# clock_board.net
KiCad netlist of a schematic drawn in EAGLE
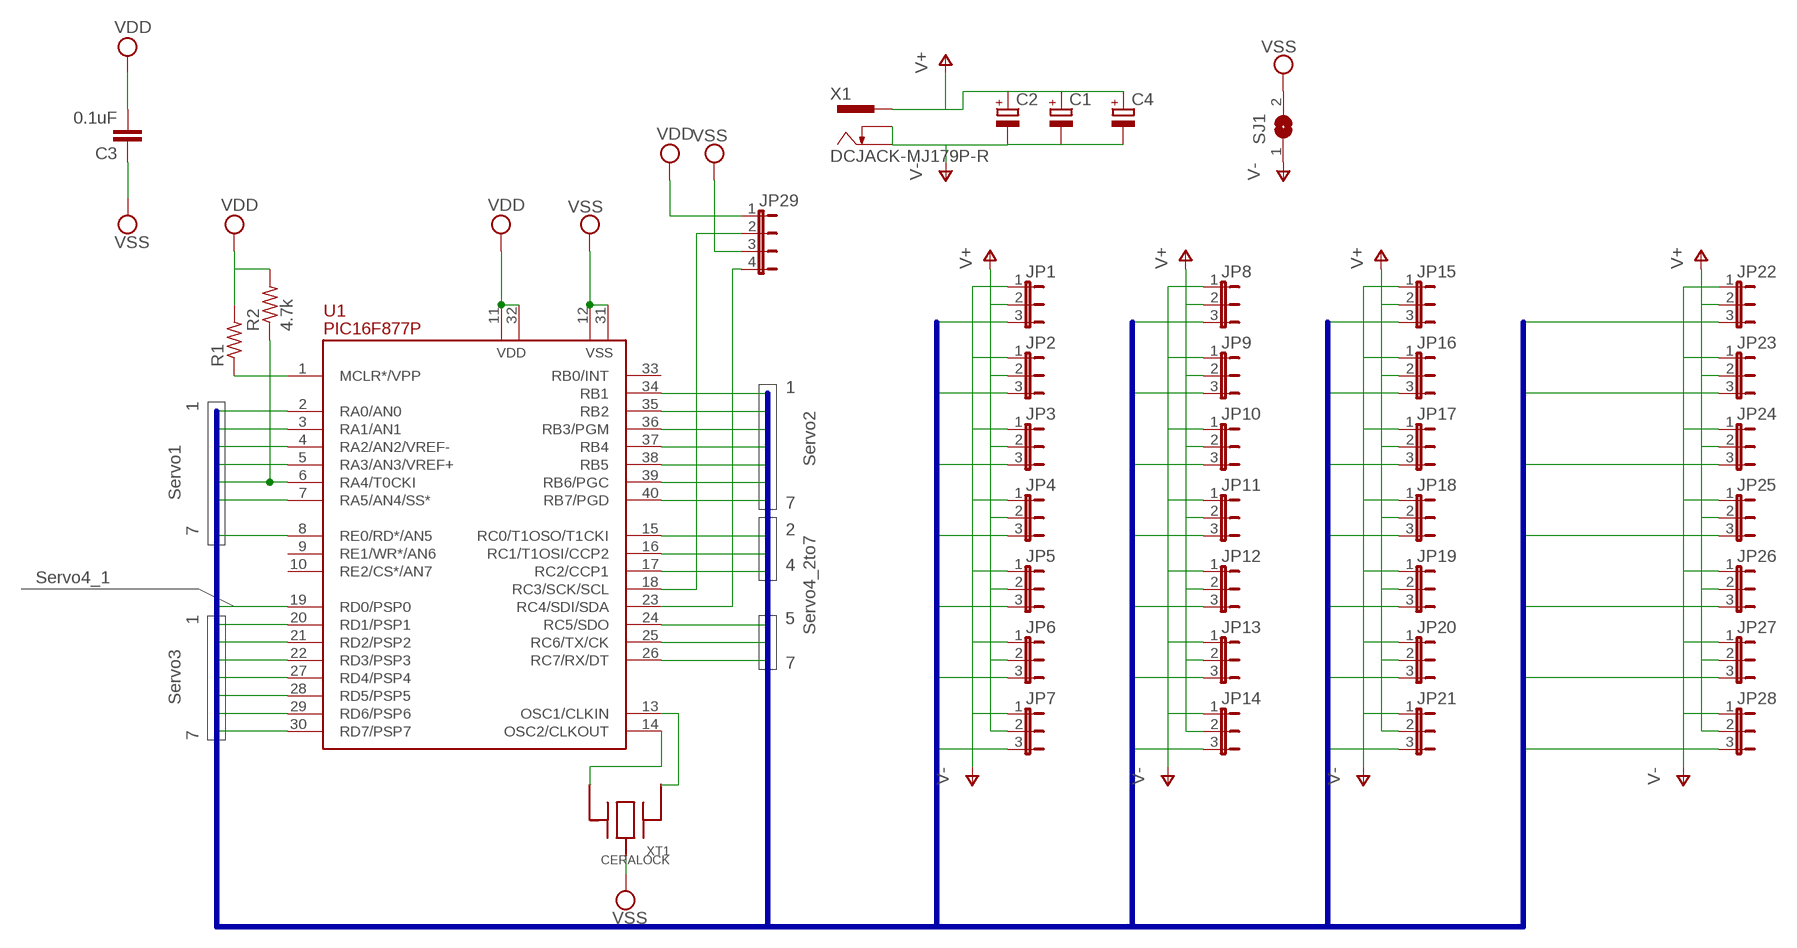
[diagram p0: schematic, sheet 1]

(export (version "E")
  (design (tool "Eeschema 10.0.6"))
  (components
    (comp (ref "C1")
      (value "CPOL-EUE2.5-5")
      (footprint "eagle-import:E2,5-5")
      (libsource (lib "eagle-import") (part "CPOL-EUE2.5-5"))
    )
    (comp (ref "C2")
      (value "CPOL-EUE2.5-5")
      (footprint "eagle-import:E2,5-5")
      (libsource (lib "eagle-import") (part "CPOL-EUE2.5-5"))
    )
    (comp (ref "C3")
      (value "0.1uF")
      (footprint "eagle-import:C025-024X044")
      (libsource (lib "eagle-import") (part "C-EU025-024X044"))
    )
    (comp (ref "C4")
      (value "CPOL-EUE2.5-5")
      (footprint "eagle-import:E2,5-5")
      (libsource (lib "eagle-import") (part "CPOL-EUE2.5-5"))
    )
    (comp (ref "JP1")
      (value "JP2E")
      (footprint "eagle-import:JP2")
      (libsource (lib "eagle-import") (part "JP2E"))
    )
    (comp (ref "JP2")
      (value "JP2E")
      (footprint "eagle-import:JP2")
      (libsource (lib "eagle-import") (part "JP2E"))
    )
    (comp (ref "JP3")
      (value "JP2E")
      (footprint "eagle-import:JP2")
      (libsource (lib "eagle-import") (part "JP2E"))
    )
    (comp (ref "JP4")
      (value "JP2E")
      (footprint "eagle-import:JP2")
      (libsource (lib "eagle-import") (part "JP2E"))
    )
    (comp (ref "JP5")
      (value "JP2E")
      (footprint "eagle-import:JP2")
      (libsource (lib "eagle-import") (part "JP2E"))
    )
    (comp (ref "JP6")
      (value "JP2E")
      (footprint "eagle-import:JP2")
      (libsource (lib "eagle-import") (part "JP2E"))
    )
    (comp (ref "JP7")
      (value "JP2E")
      (footprint "eagle-import:JP2")
      (libsource (lib "eagle-import") (part "JP2E"))
    )
    (comp (ref "JP8")
      (value "JP2E")
      (footprint "eagle-import:JP2")
      (libsource (lib "eagle-import") (part "JP2E"))
    )
    (comp (ref "JP9")
      (value "JP2E")
      (footprint "eagle-import:JP2")
      (libsource (lib "eagle-import") (part "JP2E"))
    )
    (comp (ref "JP10")
      (value "JP2E")
      (footprint "eagle-import:JP2")
      (libsource (lib "eagle-import") (part "JP2E"))
    )
    (comp (ref "JP11")
      (value "JP2E")
      (footprint "eagle-import:JP2")
      (libsource (lib "eagle-import") (part "JP2E"))
    )
    (comp (ref "JP12")
      (value "JP2E")
      (footprint "eagle-import:JP2")
      (libsource (lib "eagle-import") (part "JP2E"))
    )
    (comp (ref "JP13")
      (value "JP2E")
      (footprint "eagle-import:JP2")
      (libsource (lib "eagle-import") (part "JP2E"))
    )
    (comp (ref "JP14")
      (value "JP2E")
      (footprint "eagle-import:JP2")
      (libsource (lib "eagle-import") (part "JP2E"))
    )
    (comp (ref "JP15")
      (value "JP2E")
      (footprint "eagle-import:JP2")
      (libsource (lib "eagle-import") (part "JP2E"))
    )
    (comp (ref "JP16")
      (value "JP2E")
      (footprint "eagle-import:JP2")
      (libsource (lib "eagle-import") (part "JP2E"))
    )
    (comp (ref "JP17")
      (value "JP2E")
      (footprint "eagle-import:JP2")
      (libsource (lib "eagle-import") (part "JP2E"))
    )
    (comp (ref "JP18")
      (value "JP2E")
      (footprint "eagle-import:JP2")
      (libsource (lib "eagle-import") (part "JP2E"))
    )
    (comp (ref "JP19")
      (value "JP2E")
      (footprint "eagle-import:JP2")
      (libsource (lib "eagle-import") (part "JP2E"))
    )
    (comp (ref "JP20")
      (value "JP2E")
      (footprint "eagle-import:JP2")
      (libsource (lib "eagle-import") (part "JP2E"))
    )
    (comp (ref "JP21")
      (value "JP2E")
      (footprint "eagle-import:JP2")
      (libsource (lib "eagle-import") (part "JP2E"))
    )
    (comp (ref "JP22")
      (value "JP2E")
      (footprint "eagle-import:JP2")
      (libsource (lib "eagle-import") (part "JP2E"))
    )
    (comp (ref "JP23")
      (value "JP2E")
      (footprint "eagle-import:JP2")
      (libsource (lib "eagle-import") (part "JP2E"))
    )
    (comp (ref "JP24")
      (value "JP2E")
      (footprint "eagle-import:JP2")
      (libsource (lib "eagle-import") (part "JP2E"))
    )
    (comp (ref "JP25")
      (value "JP2E")
      (footprint "eagle-import:JP2")
      (libsource (lib "eagle-import") (part "JP2E"))
    )
    (comp (ref "JP26")
      (value "JP2E")
      (footprint "eagle-import:JP2")
      (libsource (lib "eagle-import") (part "JP2E"))
    )
    (comp (ref "JP27")
      (value "JP2E")
      (footprint "eagle-import:JP2")
      (libsource (lib "eagle-import") (part "JP2E"))
    )
    (comp (ref "JP28")
      (value "JP2E")
      (footprint "eagle-import:JP2")
      (libsource (lib "eagle-import") (part "JP2E"))
    )
    (comp (ref "JP29")
      (value "JP4E")
      (footprint "eagle-import:JP4")
      (libsource (lib "eagle-import") (part "JP4E"))
    )
    (comp (ref "R1")
      (value "R-US_0207/10")
      (footprint "eagle-import:0207_10")
      (libsource (lib "eagle-import") (part "R-US_0207/10"))
    )
    (comp (ref "R2")
      (value "4.7k")
      (footprint "eagle-import:0207_10")
      (libsource (lib "eagle-import") (part "R-US_0207/10"))
    )
    (comp (ref "SJ1")
      (value "SJW")
      (footprint "eagle-import:SJW")
      (libsource (lib "eagle-import") (part "SJW"))
    )
    (comp (ref "U1")
      (value "PIC16F877P")
      (footprint "eagle-import:DIL40")
      (libsource (lib "eagle-import") (part "PIC16F877P"))
    )
    (comp (ref "X1")
      (value "DCJACK-MJ179P-R")
      (footprint "eagle-import:MJ-179P-R")
      (libsource (lib "eagle-import") (part "DCJACK-MJ179P-R"))
    )
    (comp (ref "XT1")
      (value "CERALOCK")
      (footprint "eagle-import:CERALOCK")
      (libsource (lib "eagle-import") (part "CERALOCK"))
    )
  )
  (nets
    (net (code "1") (name "/SERVO0") (class "Default")
      (node (ref "JP1") (pin "3") (pinfunction "3_3") (pintype "passive"))
      (node (ref "U1") (pin "2") (pinfunction "RA0/AN0_2") (pintype "bidirectional"))
    )
    (net (code "2") (name "/SERVO1") (class "Default")
      (node (ref "JP2") (pin "3") (pinfunction "3_3") (pintype "passive"))
      (node (ref "U1") (pin "3") (pinfunction "RA1/AN1_3") (pintype "bidirectional"))
    )
    (net (code "3") (name "/SERVO2") (class "Default")
      (node (ref "JP3") (pin "3") (pinfunction "3_3") (pintype "passive"))
      (node (ref "U1") (pin "4") (pinfunction "RA2/AN2/VREF-_4") (pintype "bidirectional"))
    )
    (net (code "4") (name "/SERVO3") (class "Default")
      (node (ref "JP4") (pin "3") (pinfunction "3_3") (pintype "passive"))
      (node (ref "U1") (pin "5") (pinfunction "RA3/AN3/VREF+_5") (pintype "bidirectional"))
    )
    (net (code "5") (name "/SERVO4") (class "Default")
      (node (ref "JP5") (pin "3") (pinfunction "3_3") (pintype "passive"))
      (node (ref "R2") (pin "1") (pinfunction "1_1") (pintype "passive"))
      (node (ref "U1") (pin "6") (pinfunction "RA4/T0CKI_6") (pintype "bidirectional"))
    )
    (net (code "6") (name "/SERVO5") (class "Default")
      (node (ref "JP6") (pin "3") (pinfunction "3_3") (pintype "passive"))
      (node (ref "U1") (pin "7") (pinfunction "RA5/AN4/SS*_7") (pintype "bidirectional"))
    )
    (net (code "7") (name "/SERVO6") (class "Default")
      (node (ref "JP7") (pin "3") (pinfunction "3_3") (pintype "passive"))
      (node (ref "U1") (pin "8") (pinfunction "RE0/RD*/AN5_8") (pintype "bidirectional"))
    )
    (net (code "8") (name "/SERVO7") (class "Default")
      (node (ref "JP8") (pin "3") (pinfunction "3_3") (pintype "passive"))
      (node (ref "U1") (pin "34") (pinfunction "RB1_34") (pintype "bidirectional"))
    )
    (net (code "9") (name "/SERVO8") (class "Default")
      (node (ref "JP9") (pin "3") (pinfunction "3_3") (pintype "passive"))
      (node (ref "U1") (pin "35") (pinfunction "RB2_35") (pintype "bidirectional"))
    )
    (net (code "10") (name "/SERVO9") (class "Default")
      (node (ref "JP10") (pin "3") (pinfunction "3_3") (pintype "passive"))
      (node (ref "U1") (pin "36") (pinfunction "RB3/PGM_36") (pintype "bidirectional"))
    )
    (net (code "11") (name "/SERVO10") (class "Default")
      (node (ref "JP11") (pin "3") (pinfunction "3_3") (pintype "passive"))
      (node (ref "U1") (pin "37") (pinfunction "RB4_37") (pintype "bidirectional"))
    )
    (net (code "12") (name "/SERVO11") (class "Default")
      (node (ref "JP12") (pin "3") (pinfunction "3_3") (pintype "passive"))
      (node (ref "U1") (pin "38") (pinfunction "RB5_38") (pintype "bidirectional"))
    )
    (net (code "13") (name "/SERVO12") (class "Default")
      (node (ref "JP13") (pin "3") (pinfunction "3_3") (pintype "passive"))
      (node (ref "U1") (pin "39") (pinfunction "RB6/PGC_39") (pintype "bidirectional"))
    )
    (net (code "14") (name "/SERVO13") (class "Default")
      (node (ref "JP14") (pin "3") (pinfunction "3_3") (pintype "passive"))
      (node (ref "U1") (pin "40") (pinfunction "RB7/PGD_40") (pintype "bidirectional"))
    )
    (net (code "15") (name "/SERVO14") (class "Default")
      (node (ref "JP15") (pin "3") (pinfunction "3_3") (pintype "passive"))
      (node (ref "U1") (pin "20") (pinfunction "RD1/PSP1_20") (pintype "bidirectional"))
    )
    (net (code "16") (name "/SERVO15") (class "Default")
      (node (ref "JP16") (pin "3") (pinfunction "3_3") (pintype "passive"))
      (node (ref "U1") (pin "21") (pinfunction "RD2/PSP2_21") (pintype "bidirectional"))
    )
    (net (code "17") (name "/SERVO16") (class "Default")
      (node (ref "JP17") (pin "3") (pinfunction "3_3") (pintype "passive"))
      (node (ref "U1") (pin "22") (pinfunction "RD3/PSP3_22") (pintype "bidirectional"))
    )
    (net (code "18") (name "/SERVO17") (class "Default")
      (node (ref "JP18") (pin "3") (pinfunction "3_3") (pintype "passive"))
      (node (ref "U1") (pin "27") (pinfunction "RD4/PSP4_27") (pintype "bidirectional"))
    )
    (net (code "19") (name "/SERVO18") (class "Default")
      (node (ref "JP19") (pin "3") (pinfunction "3_3") (pintype "passive"))
      (node (ref "U1") (pin "28") (pinfunction "RD5/PSP5_28") (pintype "bidirectional"))
    )
    (net (code "20") (name "/SERVO19") (class "Default")
      (node (ref "JP20") (pin "3") (pinfunction "3_3") (pintype "passive"))
      (node (ref "U1") (pin "29") (pinfunction "RD6/PSP6_29") (pintype "bidirectional"))
    )
    (net (code "21") (name "/SERVO20") (class "Default")
      (node (ref "JP21") (pin "3") (pinfunction "3_3") (pintype "passive"))
      (node (ref "U1") (pin "30") (pinfunction "RD7/PSP7_30") (pintype "bidirectional"))
    )
    (net (code "22") (name "/SERVO21") (class "Default")
      (node (ref "JP22") (pin "3") (pinfunction "3_3") (pintype "passive"))
      (node (ref "U1") (pin "19") (pinfunction "RD0/PSP0_19") (pintype "bidirectional"))
    )
    (net (code "23") (name "/SERVO22") (class "Default")
      (node (ref "JP23") (pin "3") (pinfunction "3_3") (pintype "passive"))
      (node (ref "U1") (pin "15") (pinfunction "RC0/T1OSO/T1CKI_15") (pintype "bidirectional"))
    )
    (net (code "24") (name "/SERVO23") (class "Default")
      (node (ref "JP24") (pin "3") (pinfunction "3_3") (pintype "passive"))
      (node (ref "U1") (pin "16") (pinfunction "RC1/T1OSI/CCP2_16") (pintype "bidirectional"))
    )
    (net (code "25") (name "/SERVO24") (class "Default")
      (node (ref "JP25") (pin "3") (pinfunction "3_3") (pintype "passive"))
      (node (ref "U1") (pin "17") (pinfunction "RC2/CCP1_17") (pintype "bidirectional"))
    )
    (net (code "26") (name "/SERVO25") (class "Default")
      (node (ref "JP26") (pin "3") (pinfunction "3_3") (pintype "passive"))
      (node (ref "U1") (pin "24") (pinfunction "RC5/SDO_24") (pintype "bidirectional"))
    )
    (net (code "27") (name "/SERVO26") (class "Default")
      (node (ref "JP27") (pin "3") (pinfunction "3_3") (pintype "passive"))
      (node (ref "U1") (pin "25") (pinfunction "RC6/TX/CK_25") (pintype "bidirectional"))
    )
    (net (code "28") (name "/SERVO27") (class "Default")
      (node (ref "JP28") (pin "3") (pinfunction "3_3") (pintype "passive"))
      (node (ref "U1") (pin "26") (pinfunction "RC7/RX/DT_26") (pintype "bidirectional"))
    )
    (net (code "29") (name "Net-(U1-MCLR*{slash}VPP)") (class "Default")
      (node (ref "R1") (pin "1") (pinfunction "1_1") (pintype "passive"))
      (node (ref "U1") (pin "1") (pinfunction "MCLR*/VPP_1") (pintype "input"))
    )
    (net (code "30") (name "Net-(U1-OSC1{slash}CLKIN)") (class "Default")
      (node (ref "U1") (pin "13") (pinfunction "OSC1/CLKIN_13") (pintype "input"))
      (node (ref "XT1") (pin "P$1") (pinfunction "1_P$1") (pintype "passive"))
    )
    (net (code "31") (name "Net-(U1-OSC2{slash}CLKOUT)") (class "Default")
      (node (ref "U1") (pin "14") (pinfunction "OSC2/CLKOUT_14") (pintype "output"))
      (node (ref "XT1") (pin "P$3") (pinfunction "3_P$3") (pintype "passive"))
    )
    (net (code "32") (name "Net-(U1-RC3{slash}SCK{slash}SCL)") (class "Default")
      (node (ref "JP29") (pin "2") (pinfunction "2_2") (pintype "passive"))
      (node (ref "U1") (pin "18") (pinfunction "RC3/SCK/SCL_18") (pintype "bidirectional"))
    )
    (net (code "33") (name "Net-(U1-RC4{slash}SDI{slash}SDA)") (class "Default")
      (node (ref "JP29") (pin "4") (pinfunction "4_4") (pintype "passive"))
      (node (ref "U1") (pin "23") (pinfunction "RC4/SDI/SDA_23") (pintype "bidirectional"))
    )
    (net (code "34") (name "V+") (class "Default")
      (node (ref "C1") (pin "+") (pinfunction "+_+") (pintype "passive"))
      (node (ref "C2") (pin "+") (pinfunction "+_+") (pintype "passive"))
      (node (ref "C4") (pin "+") (pinfunction "+_+") (pintype "passive"))
      (node (ref "JP1") (pin "2") (pinfunction "2_2") (pintype "passive"))
      (node (ref "JP10") (pin "2") (pinfunction "2_2") (pintype "passive"))
      (node (ref "JP11") (pin "2") (pinfunction "2_2") (pintype "passive"))
      (node (ref "JP12") (pin "2") (pinfunction "2_2") (pintype "passive"))
      (node (ref "JP13") (pin "2") (pinfunction "2_2") (pintype "passive"))
      (node (ref "JP14") (pin "2") (pinfunction "2_2") (pintype "passive"))
      (node (ref "JP15") (pin "2") (pinfunction "2_2") (pintype "passive"))
      (node (ref "JP16") (pin "2") (pinfunction "2_2") (pintype "passive"))
      (node (ref "JP17") (pin "2") (pinfunction "2_2") (pintype "passive"))
      (node (ref "JP18") (pin "2") (pinfunction "2_2") (pintype "passive"))
      (node (ref "JP19") (pin "2") (pinfunction "2_2") (pintype "passive"))
      (node (ref "JP2") (pin "2") (pinfunction "2_2") (pintype "passive"))
      (node (ref "JP20") (pin "2") (pinfunction "2_2") (pintype "passive"))
      (node (ref "JP21") (pin "2") (pinfunction "2_2") (pintype "passive"))
      (node (ref "JP22") (pin "2") (pinfunction "2_2") (pintype "passive"))
      (node (ref "JP23") (pin "2") (pinfunction "2_2") (pintype "passive"))
      (node (ref "JP24") (pin "2") (pinfunction "2_2") (pintype "passive"))
      (node (ref "JP25") (pin "2") (pinfunction "2_2") (pintype "passive"))
      (node (ref "JP26") (pin "2") (pinfunction "2_2") (pintype "passive"))
      (node (ref "JP27") (pin "2") (pinfunction "2_2") (pintype "passive"))
      (node (ref "JP28") (pin "2") (pinfunction "2_2") (pintype "passive"))
      (node (ref "JP3") (pin "2") (pinfunction "2_2") (pintype "passive"))
      (node (ref "JP4") (pin "2") (pinfunction "2_2") (pintype "passive"))
      (node (ref "JP5") (pin "2") (pinfunction "2_2") (pintype "passive"))
      (node (ref "JP6") (pin "2") (pinfunction "2_2") (pintype "passive"))
      (node (ref "JP7") (pin "2") (pinfunction "2_2") (pintype "passive"))
      (node (ref "JP8") (pin "2") (pinfunction "2_2") (pintype "passive"))
      (node (ref "JP9") (pin "2") (pinfunction "2_2") (pintype "passive"))
      (node (ref "X1") (pin "1") (pinfunction "1_1") (pintype "passive"))
    )
    (net (code "35") (name "V-") (class "Default")
      (node (ref "C1") (pin "-") (pinfunction "-_-") (pintype "passive"))
      (node (ref "C2") (pin "-") (pinfunction "-_-") (pintype "passive"))
      (node (ref "C4") (pin "-") (pinfunction "-_-") (pintype "passive"))
      (node (ref "JP1") (pin "1") (pinfunction "1_1") (pintype "passive"))
      (node (ref "JP10") (pin "1") (pinfunction "1_1") (pintype "passive"))
      (node (ref "JP11") (pin "1") (pinfunction "1_1") (pintype "passive"))
      (node (ref "JP12") (pin "1") (pinfunction "1_1") (pintype "passive"))
      (node (ref "JP13") (pin "1") (pinfunction "1_1") (pintype "passive"))
      (node (ref "JP14") (pin "1") (pinfunction "1_1") (pintype "passive"))
      (node (ref "JP15") (pin "1") (pinfunction "1_1") (pintype "passive"))
      (node (ref "JP16") (pin "1") (pinfunction "1_1") (pintype "passive"))
      (node (ref "JP17") (pin "1") (pinfunction "1_1") (pintype "passive"))
      (node (ref "JP18") (pin "1") (pinfunction "1_1") (pintype "passive"))
      (node (ref "JP19") (pin "1") (pinfunction "1_1") (pintype "passive"))
      (node (ref "JP2") (pin "1") (pinfunction "1_1") (pintype "passive"))
      (node (ref "JP20") (pin "1") (pinfunction "1_1") (pintype "passive"))
      (node (ref "JP21") (pin "1") (pinfunction "1_1") (pintype "passive"))
      (node (ref "JP22") (pin "1") (pinfunction "1_1") (pintype "passive"))
      (node (ref "JP23") (pin "1") (pinfunction "1_1") (pintype "passive"))
      (node (ref "JP24") (pin "1") (pinfunction "1_1") (pintype "passive"))
      (node (ref "JP25") (pin "1") (pinfunction "1_1") (pintype "passive"))
      (node (ref "JP26") (pin "1") (pinfunction "1_1") (pintype "passive"))
      (node (ref "JP27") (pin "1") (pinfunction "1_1") (pintype "passive"))
      (node (ref "JP28") (pin "1") (pinfunction "1_1") (pintype "passive"))
      (node (ref "JP3") (pin "1") (pinfunction "1_1") (pintype "passive"))
      (node (ref "JP4") (pin "1") (pinfunction "1_1") (pintype "passive"))
      (node (ref "JP5") (pin "1") (pinfunction "1_1") (pintype "passive"))
      (node (ref "JP6") (pin "1") (pinfunction "1_1") (pintype "passive"))
      (node (ref "JP7") (pin "1") (pinfunction "1_1") (pintype "passive"))
      (node (ref "JP8") (pin "1") (pinfunction "1_1") (pintype "passive"))
      (node (ref "JP9") (pin "1") (pinfunction "1_1") (pintype "passive"))
      (node (ref "SJ1") (pin "1") (pinfunction "1_1") (pintype "passive"))
      (node (ref "X1") (pin "2") (pinfunction "2_2") (pintype "passive"))
      (node (ref "X1") (pin "3") (pinfunction "3_3") (pintype "passive"))
    )
    (net (code "36") (name "VDD") (class "Default")
      (node (ref "C3") (pin "2") (pinfunction "2_2") (pintype "passive"))
      (node (ref "JP29") (pin "1") (pinfunction "1_1") (pintype "passive"))
      (node (ref "R1") (pin "2") (pinfunction "2_2") (pintype "passive"))
      (node (ref "R2") (pin "2") (pinfunction "2_2") (pintype "passive"))
      (node (ref "U1") (pin "11") (pinfunction "VDD_11") (pintype "bidirectional"))
      (node (ref "U1") (pin "32") (pinfunction "VDD_32") (pintype "bidirectional"))
    )
    (net (code "37") (name "VSS") (class "Default")
      (node (ref "C3") (pin "1") (pinfunction "1_1") (pintype "passive"))
      (node (ref "JP29") (pin "3") (pinfunction "3_3") (pintype "passive"))
      (node (ref "SJ1") (pin "2") (pinfunction "2_2") (pintype "passive"))
      (node (ref "U1") (pin "12") (pinfunction "VSS_12") (pintype "bidirectional"))
      (node (ref "U1") (pin "31") (pinfunction "VSS_31") (pintype "bidirectional"))
      (node (ref "XT1") (pin "P$2") (pinfunction "2_P$2") (pintype "passive"))
    )
    (net (code "38") (name "unconnected-(U1-RB0{slash}INT-Pad33)") (class "Default")
      (node (ref "U1") (pin "33") (pinfunction "RB0/INT_33") (pintype "bidirectional"))
    )
    (net (code "39") (name "unconnected-(U1-RE1{slash}WR*{slash}AN6-Pad9)") (class "Default")
      (node (ref "U1") (pin "9") (pinfunction "RE1/WR*/AN6_9") (pintype "bidirectional"))
    )
    (net (code "40") (name "unconnected-(U1-RE2{slash}CS*{slash}AN7-Pad10)") (class "Default")
      (node (ref "U1") (pin "10") (pinfunction "RE2/CS*/AN7_10") (pintype "bidirectional"))
    )
  )
)
